# 10-DigitalToAnalogConvert.net
KiCad netlist of a schematic drawn in Altium Designer
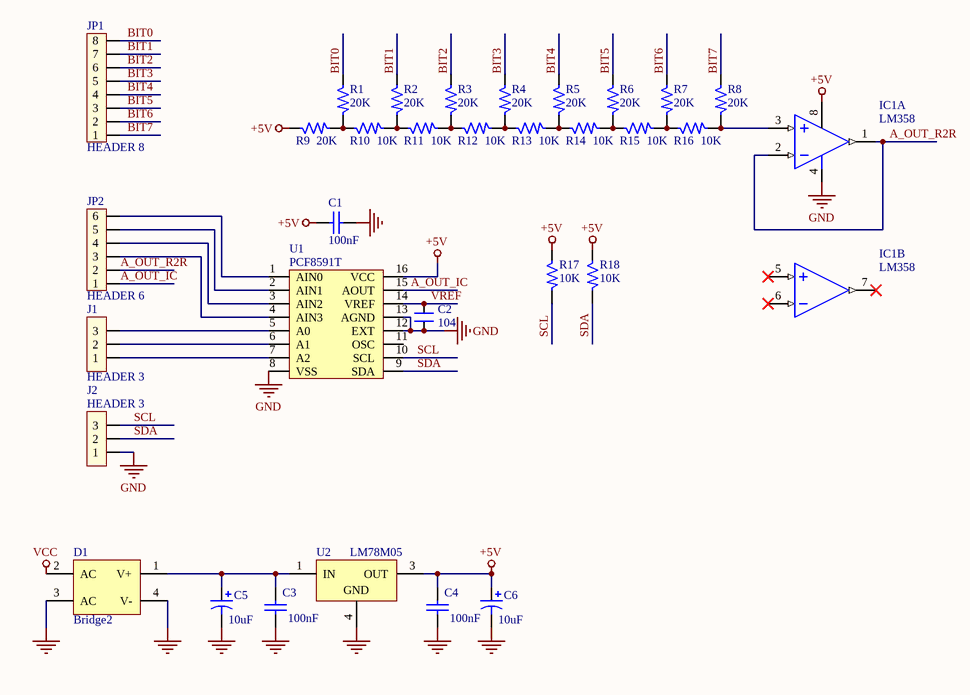
[diagram p0: 10-DigitalToAnalogConvert.SchDoc]

(export (version "E")
  (design (tool "Eeschema 10.0.6"))
  (components
    (comp (ref "C1")
      (value "100nF")
      (footprint "RAD-0.3")
      (description "Capacitor")
      (fields (field (name "Comment") "104") (field (name "PUBLISHER") "Altium Limited"))
      (libsource (lib "Miscellaneous Devices") (part "Cap"))
    )
    (comp (ref "C2")
      (value "104")
      (footprint "C-0805")
      (fields (field (name "DESIGNED BY") "VanDungEvn"))
      (libsource (lib "syhaunguyen") (part "CN"))
    )
    (comp (ref "C3")
      (value "100nF")
      (footprint "RAD-0.3")
      (description "Capacitor")
      (fields (field (name "Comment") "104") (field (name "PUBLISHER") "Altium Limited"))
      (libsource (lib "Miscellaneous Devices") (part "Cap"))
    )
    (comp (ref "C4")
      (value "100nF")
      (footprint "RAD-0.3")
      (description "Capacitor")
      (fields (field (name "Comment") "104") (field (name "PUBLISHER") "Altium Limited"))
      (libsource (lib "Miscellaneous Devices") (part "Cap"))
    )
    (comp (ref "C5")
      (value "10uF")
      (footprint "RB7.6-15")
      (description "Polarized Capacitor (Radial)")
      (fields (field (name "Comment") "10uF/16V") (field (name "PUBLISHER") "Altium Limited"))
      (libsource (lib "Miscellaneous Devices") (part "Cap Pol1"))
    )
    (comp (ref "C6")
      (value "10uF")
      (footprint "RB7.6-15")
      (description "Polarized Capacitor (Radial)")
      (fields (field (name "Comment") "10uF/16V") (field (name "PUBLISHER") "Altium Limited"))
      (libsource (lib "Miscellaneous Devices") (part "Cap Pol1"))
    )
    (comp (ref "D1")
      (value "Bridge2")
      (footprint "D-46_6A")
      (description "Diode Bridge")
      (fields (field (name "PUBLISHER") "Altium Limited"))
      (libsource (lib "Miscellaneous Devices") (part "Bridge2"))
    )
    (comp (ref "IC1")
      (value "LM358")
      (footprint "SOP-8")
      (description "Low-Power Dual Operational Amplifier")
      (libsource (lib "syhaunguyen") (part "LM358"))
    )
    (comp (ref "J1")
      (value "HEADER 3")
      (footprint "JP3")
      (description "Jumper 3")
      (libsource (lib "syhaunguyen") (part "JP3"))
    )
    (comp (ref "J2")
      (value "HEADER 3")
      (footprint "JP3")
      (description "Jumper 3")
      (libsource (lib "syhaunguyen") (part "JP3"))
    )
    (comp (ref "JP1")
      (value "HEADER 8")
      (footprint "JP8")
      (description "JP8 PIN")
      (libsource (lib "syhaunguyen") (part "JP8"))
    )
    (comp (ref "JP2")
      (value "HEADER 6")
      (footprint "JP6")
      (description "JP6 PIN")
      (libsource (lib "syhaunguyen") (part "JP6"))
    )
    (comp (ref "R1")
      (value "20K")
      (footprint "R-0805")
      (description "Resistor 1/4W")
      (libsource (lib "syhaunguyen") (part "R"))
    )
    (comp (ref "R2")
      (value "20K")
      (footprint "R-0805")
      (description "Resistor 1/4W")
      (libsource (lib "syhaunguyen") (part "R"))
    )
    (comp (ref "R3")
      (value "20K")
      (footprint "R-0805")
      (description "Resistor 1/4W")
      (libsource (lib "syhaunguyen") (part "R"))
    )
    (comp (ref "R4")
      (value "20K")
      (footprint "R-0805")
      (description "Resistor 1/4W")
      (libsource (lib "syhaunguyen") (part "R"))
    )
    (comp (ref "R5")
      (value "20K")
      (footprint "R-0805")
      (description "Resistor 1/4W")
      (libsource (lib "syhaunguyen") (part "R"))
    )
    (comp (ref "R6")
      (value "20K")
      (footprint "R-0805")
      (description "Resistor 1/4W")
      (libsource (lib "syhaunguyen") (part "R"))
    )
    (comp (ref "R7")
      (value "20K")
      (footprint "R-0805")
      (description "Resistor 1/4W")
      (libsource (lib "syhaunguyen") (part "R"))
    )
    (comp (ref "R8")
      (value "20K")
      (footprint "R-0805")
      (description "Resistor 1/4W")
      (libsource (lib "syhaunguyen") (part "R"))
    )
    (comp (ref "R9")
      (value "20K")
      (footprint "R-0805")
      (description "Resistor 1/4W")
      (libsource (lib "syhaunguyen") (part "R"))
    )
    (comp (ref "R10")
      (value "10K")
      (footprint "R-0805")
      (description "Resistor 1/4W")
      (libsource (lib "syhaunguyen") (part "R"))
    )
    (comp (ref "R11")
      (value "10K")
      (footprint "R-0805")
      (description "Resistor 1/4W")
      (libsource (lib "syhaunguyen") (part "R"))
    )
    (comp (ref "R12")
      (value "10K")
      (footprint "R-0805")
      (description "Resistor 1/4W")
      (libsource (lib "syhaunguyen") (part "R"))
    )
    (comp (ref "R13")
      (value "10K")
      (footprint "R-0805")
      (description "Resistor 1/4W")
      (libsource (lib "syhaunguyen") (part "R"))
    )
    (comp (ref "R14")
      (value "10K")
      (footprint "R-0805")
      (description "Resistor 1/4W")
      (libsource (lib "syhaunguyen") (part "R"))
    )
    (comp (ref "R15")
      (value "10K")
      (footprint "R-0805")
      (description "Resistor 1/4W")
      (libsource (lib "syhaunguyen") (part "R"))
    )
    (comp (ref "R16")
      (value "10K")
      (footprint "R-0805")
      (description "Resistor 1/4W")
      (libsource (lib "syhaunguyen") (part "R"))
    )
    (comp (ref "R17")
      (value "10K")
      (footprint "R-0805")
      (description "Resistor 1/4W")
      (libsource (lib "syhaunguyen") (part "R"))
    )
    (comp (ref "R18")
      (value "10K")
      (footprint "R-0805")
      (description "Resistor 1/4W")
      (libsource (lib "syhaunguyen") (part "R"))
    )
    (comp (ref "U1")
      (value "PCF8591T")
      (footprint "SO-16")
      (libsource (lib "doAnTotNghiep2017Lib") (part "PCF8591T"))
    )
    (comp (ref "U2")
      (value "LM78M05")
      (footprint "NDP0003B_M")
      (description "3-Terminal Positive Voltage Regulators, 3-pin TO-252")
      (fields (field (name "MANUFACTURER") "Texas Instruments") (field (name "Comment") "LM78M05CDTX"))
      (libsource (lib "Altium Content Vault") (part "CMP-0062-00204-3"))
    )
  )
  (nets
    (net (code "1") (name "+5V") (class "Default")
      (node (ref "C1") (pin "1") (pinfunction "1_1") (pintype "passive"))
      (node (ref "C4") (pin "1") (pinfunction "1_1") (pintype "passive"))
      (node (ref "C6") (pin "1") (pinfunction "1_1") (pintype "passive"))
      (node (ref "IC1") (pin "8") (pinfunction "+V_8") (pintype "passive"))
      (node (ref "R17") (pin "1") (pinfunction "1_1") (pintype "passive"))
      (node (ref "R18") (pin "1") (pinfunction "1_1") (pintype "passive"))
      (node (ref "R9") (pin "1") (pinfunction "1_1") (pintype "passive"))
      (node (ref "U1") (pin "16") (pinfunction "VCC_16") (pintype "passive"))
      (node (ref "U2") (pin "3") (pinfunction "OUT_3") (pintype "power_in"))
    )
    (net (code "2") (name "/A_OUT_IC") (class "Default")
      (node (ref "JP2") (pin "1") (pinfunction "1_1") (pintype "passive"))
      (node (ref "U1") (pin "15") (pinfunction "AOUT_15") (pintype "passive"))
    )
    (net (code "3") (name "/A_OUT_R2R") (class "Default")
      (node (ref "IC1") (pin "1") (pinfunction "OUT_1") (pintype "output"))
      (node (ref "IC1") (pin "2") (pinfunction "IN-_2") (pintype "input"))
      (node (ref "JP2") (pin "2") (pinfunction "2_2") (pintype "passive"))
    )
    (net (code "4") (name "/BIT0") (class "Default")
      (node (ref "JP1") (pin "8") (pinfunction "8_8") (pintype "passive"))
      (node (ref "R1") (pin "1") (pinfunction "1_1") (pintype "passive"))
    )
    (net (code "5") (name "/BIT1") (class "Default")
      (node (ref "JP1") (pin "7") (pinfunction "7_7") (pintype "passive"))
      (node (ref "R2") (pin "1") (pinfunction "1_1") (pintype "passive"))
    )
    (net (code "6") (name "/BIT2") (class "Default")
      (node (ref "JP1") (pin "6") (pinfunction "6_6") (pintype "passive"))
      (node (ref "R3") (pin "1") (pinfunction "1_1") (pintype "passive"))
    )
    (net (code "7") (name "/BIT3") (class "Default")
      (node (ref "JP1") (pin "5") (pinfunction "5_5") (pintype "passive"))
      (node (ref "R4") (pin "1") (pinfunction "1_1") (pintype "passive"))
    )
    (net (code "8") (name "/BIT4") (class "Default")
      (node (ref "JP1") (pin "4") (pinfunction "4_4") (pintype "passive"))
      (node (ref "R5") (pin "1") (pinfunction "1_1") (pintype "passive"))
    )
    (net (code "9") (name "/BIT5") (class "Default")
      (node (ref "JP1") (pin "3") (pinfunction "3_3") (pintype "passive"))
      (node (ref "R6") (pin "1") (pinfunction "1_1") (pintype "passive"))
    )
    (net (code "10") (name "/BIT6") (class "Default")
      (node (ref "JP1") (pin "2") (pinfunction "2_2") (pintype "passive"))
      (node (ref "R7") (pin "1") (pinfunction "1_1") (pintype "passive"))
    )
    (net (code "11") (name "/BIT7") (class "Default")
      (node (ref "JP1") (pin "1") (pinfunction "1_1") (pintype "passive"))
      (node (ref "R8") (pin "1") (pinfunction "1_1") (pintype "passive"))
    )
    (net (code "12") (name "/SCL") (class "Default")
      (node (ref "J2") (pin "3") (pinfunction "3_3") (pintype "passive"))
      (node (ref "R17") (pin "2") (pinfunction "2_2") (pintype "passive"))
      (node (ref "U1") (pin "10") (pinfunction "SCL_10") (pintype "passive"))
    )
    (net (code "13") (name "/SDA") (class "Default")
      (node (ref "J2") (pin "2") (pinfunction "2_2") (pintype "passive"))
      (node (ref "R18") (pin "2") (pinfunction "2_2") (pintype "passive"))
      (node (ref "U1") (pin "9") (pinfunction "SDA_9") (pintype "passive"))
    )
    (net (code "14") (name "/VREF") (class "Default")
      (node (ref "C2") (pin "2") (pinfunction "2_2") (pintype "passive"))
      (node (ref "U1") (pin "14") (pinfunction "VREF_14") (pintype "passive"))
    )
    (net (code "15") (name "GND") (class "Default")
      (node (ref "C1") (pin "2") (pinfunction "2_2") (pintype "passive"))
      (node (ref "C2") (pin "1") (pinfunction "1_1") (pintype "passive"))
      (node (ref "C3") (pin "2") (pinfunction "2_2") (pintype "passive"))
      (node (ref "C4") (pin "2") (pinfunction "2_2") (pintype "passive"))
      (node (ref "C5") (pin "2") (pinfunction "2_2") (pintype "passive"))
      (node (ref "C6") (pin "2") (pinfunction "2_2") (pintype "passive"))
      (node (ref "D1") (pin "3") (pinfunction "AC_3") (pintype "passive"))
      (node (ref "D1") (pin "4") (pinfunction "V-_4") (pintype "passive"))
      (node (ref "IC1") (pin "4") (pinfunction "-V_4") (pintype "passive"))
      (node (ref "J2") (pin "1") (pinfunction "1_1") (pintype "passive"))
      (node (ref "U1") (pin "12") (pinfunction "EXT_12") (pintype "passive"))
      (node (ref "U1") (pin "13") (pinfunction "AGND_13") (pintype "passive"))
      (node (ref "U1") (pin "8") (pinfunction "VSS_8") (pintype "passive"))
      (node (ref "U2") (pin "4") (pinfunction "GND_4") (pintype "power_in"))
    )
    (net (code "16") (name "Net-(D1-V+)") (class "Default")
      (node (ref "C3") (pin "1") (pinfunction "1_1") (pintype "passive"))
      (node (ref "C5") (pin "1") (pinfunction "1_1") (pintype "passive"))
      (node (ref "D1") (pin "1") (pinfunction "V+_1") (pintype "passive"))
      (node (ref "U2") (pin "1") (pinfunction "IN_1") (pintype "power_in"))
    )
    (net (code "17") (name "Net-(IC1A-IN+)") (class "Default")
      (node (ref "IC1") (pin "3") (pinfunction "IN+_3") (pintype "input"))
      (node (ref "R16") (pin "2") (pinfunction "2_2") (pintype "passive"))
      (node (ref "R8") (pin "2") (pinfunction "2_2") (pintype "passive"))
    )
    (net (code "18") (name "Net-(R1-Pad2)") (class "Default")
      (node (ref "R1") (pin "2") (pinfunction "2_2") (pintype "passive"))
      (node (ref "R10") (pin "1") (pinfunction "1_1") (pintype "passive"))
      (node (ref "R9") (pin "2") (pinfunction "2_2") (pintype "passive"))
    )
    (net (code "19") (name "Net-(R10-Pad2)") (class "Default")
      (node (ref "R10") (pin "2") (pinfunction "2_2") (pintype "passive"))
      (node (ref "R11") (pin "1") (pinfunction "1_1") (pintype "passive"))
      (node (ref "R2") (pin "2") (pinfunction "2_2") (pintype "passive"))
    )
    (net (code "20") (name "Net-(R11-Pad2)") (class "Default")
      (node (ref "R11") (pin "2") (pinfunction "2_2") (pintype "passive"))
      (node (ref "R12") (pin "1") (pinfunction "1_1") (pintype "passive"))
      (node (ref "R3") (pin "2") (pinfunction "2_2") (pintype "passive"))
    )
    (net (code "21") (name "Net-(R12-Pad2)") (class "Default")
      (node (ref "R12") (pin "2") (pinfunction "2_2") (pintype "passive"))
      (node (ref "R13") (pin "1") (pinfunction "1_1") (pintype "passive"))
      (node (ref "R4") (pin "2") (pinfunction "2_2") (pintype "passive"))
    )
    (net (code "22") (name "Net-(R13-Pad2)") (class "Default")
      (node (ref "R13") (pin "2") (pinfunction "2_2") (pintype "passive"))
      (node (ref "R14") (pin "1") (pinfunction "1_1") (pintype "passive"))
      (node (ref "R5") (pin "2") (pinfunction "2_2") (pintype "passive"))
    )
    (net (code "23") (name "Net-(R14-Pad2)") (class "Default")
      (node (ref "R14") (pin "2") (pinfunction "2_2") (pintype "passive"))
      (node (ref "R15") (pin "1") (pinfunction "1_1") (pintype "passive"))
      (node (ref "R6") (pin "2") (pinfunction "2_2") (pintype "passive"))
    )
    (net (code "24") (name "Net-(R15-Pad2)") (class "Default")
      (node (ref "R15") (pin "2") (pinfunction "2_2") (pintype "passive"))
      (node (ref "R16") (pin "1") (pinfunction "1_1") (pintype "passive"))
      (node (ref "R7") (pin "2") (pinfunction "2_2") (pintype "passive"))
    )
    (net (code "25") (name "Net-(U1-A0)") (class "Default")
      (node (ref "J1") (pin "3") (pinfunction "3_3") (pintype "passive"))
      (node (ref "U1") (pin "5") (pinfunction "A0_5") (pintype "passive"))
    )
    (net (code "26") (name "Net-(U1-A1)") (class "Default")
      (node (ref "J1") (pin "2") (pinfunction "2_2") (pintype "passive"))
      (node (ref "U1") (pin "6") (pinfunction "A1_6") (pintype "passive"))
    )
    (net (code "27") (name "Net-(U1-A2)") (class "Default")
      (node (ref "J1") (pin "1") (pinfunction "1_1") (pintype "passive"))
      (node (ref "U1") (pin "7") (pinfunction "A2_7") (pintype "passive"))
    )
    (net (code "28") (name "Net-(U1-AIN0)") (class "Default")
      (node (ref "JP2") (pin "6") (pinfunction "6_6") (pintype "passive"))
      (node (ref "U1") (pin "1") (pinfunction "AIN0_1") (pintype "passive"))
    )
    (net (code "29") (name "Net-(U1-AIN1)") (class "Default")
      (node (ref "JP2") (pin "5") (pinfunction "5_5") (pintype "passive"))
      (node (ref "U1") (pin "2") (pinfunction "AIN1_2") (pintype "passive"))
    )
    (net (code "30") (name "Net-(U1-AIN2)") (class "Default")
      (node (ref "JP2") (pin "4") (pinfunction "4_4") (pintype "passive"))
      (node (ref "U1") (pin "3") (pinfunction "AIN2_3") (pintype "passive"))
    )
    (net (code "31") (name "Net-(U1-AIN3)") (class "Default")
      (node (ref "JP2") (pin "3") (pinfunction "3_3") (pintype "passive"))
      (node (ref "U1") (pin "4") (pinfunction "AIN3_4") (pintype "passive"))
    )
    (net (code "32") (name "VCC") (class "Default")
      (node (ref "D1") (pin "2") (pinfunction "AC_2") (pintype "passive"))
    )
    (net (code "33") (name "unconnected-(IC1B-IN+-Pad5)") (class "Default")
      (node (ref "IC1") (pin "5") (pinfunction "IN+_5") (pintype "input+no_connect"))
    )
    (net (code "34") (name "unconnected-(IC1B-IN--Pad6)") (class "Default")
      (node (ref "IC1") (pin "6") (pinfunction "IN-_6") (pintype "input+no_connect"))
    )
    (net (code "35") (name "unconnected-(IC1B-OUT-Pad7)") (class "Default")
      (node (ref "IC1") (pin "7") (pinfunction "OUT_7") (pintype "output+no_connect"))
    )
    (net (code "36") (name "unconnected-(U1-OSC-Pad11)") (class "Default")
      (node (ref "U1") (pin "11") (pinfunction "OSC_11") (pintype "passive"))
    )
  )
)
